# LTC3115_-_przetwornica_ogniwo.net
KiCad netlist of a schematic drawn in EAGLE
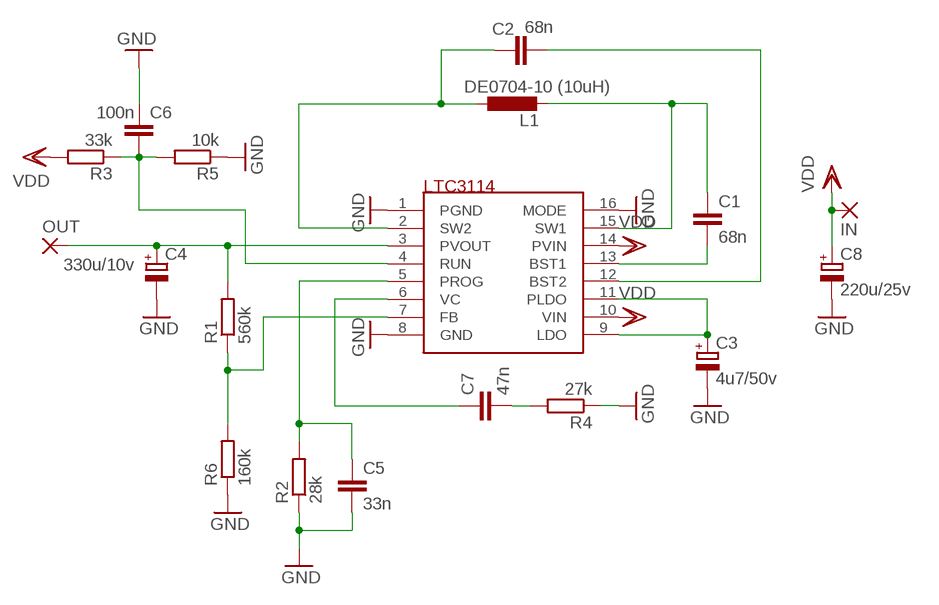
[diagram p0: schematic, sheet 1]

(export (version "E")
  (design (tool "Eeschema 10.0.6"))
  (components
    (comp (ref "C1")
      (value "68n")
      (footprint "eagle-import:C0805")
      (libsource (lib "eagle-import") (part "resistor_C-EUC0805"))
    )
    (comp (ref "C2")
      (value "68n")
      (footprint "eagle-import:C0805")
      (libsource (lib "eagle-import") (part "resistor_C-EUC0805"))
    )
    (comp (ref "C3")
      (value "4u7/50v")
      (footprint "eagle-import:E2,5-6E")
      (libsource (lib "eagle-import") (part "CPOL-EUE2,5-6E"))
    )
    (comp (ref "C4")
      (value "330u/10v")
      (footprint "eagle-import:E2,5-6E")
      (libsource (lib "eagle-import") (part "CPOL-EUE2,5-6E"))
    )
    (comp (ref "C5")
      (value "33n")
      (footprint "eagle-import:C0805")
      (libsource (lib "eagle-import") (part "C-EUC0805"))
    )
    (comp (ref "C6")
      (value "100n")
      (footprint "eagle-import:C0805")
      (libsource (lib "eagle-import") (part "C-EUC0805"))
    )
    (comp (ref "C7")
      (value "47n")
      (footprint "eagle-import:C0805")
      (libsource (lib "eagle-import") (part "C-EUC0805"))
    )
    (comp (ref "C8")
      (value "220u/25v")
      (footprint "eagle-import:E2,5-6E")
      (libsource (lib "eagle-import") (part "CPOL-EUE2,5-6E"))
    )
    (comp (ref "IN")
      (value "1,6/0,8")
      (footprint "eagle-import:1,6_0,8")
      (libsource (lib "eagle-import") (part "1,6/0,8"))
    )
    (comp (ref "L1")
      (value "DE0704-10 (10uH)")
      (footprint "eagle-import:L3225M")
      (libsource (lib "eagle-import") (part "L-EUL3225M"))
    )
    (comp (ref "OUT")
      (value "1,6/0,8")
      (footprint "eagle-import:1,6_0,8")
      (libsource (lib "eagle-import") (part "1,6/0,8"))
    )
    (comp (ref "R1")
      (value "560k")
      (footprint "eagle-import:M0805")
      (libsource (lib "eagle-import") (part "R-EU_M0805"))
    )
    (comp (ref "R2")
      (value "28k")
      (footprint "eagle-import:M0805")
      (libsource (lib "eagle-import") (part "R-EU_M0805"))
    )
    (comp (ref "R3")
      (value "33k")
      (footprint "eagle-import:M0805")
      (libsource (lib "eagle-import") (part "R-EU_M0805"))
    )
    (comp (ref "R4")
      (value "27k")
      (footprint "eagle-import:M0805")
      (libsource (lib "eagle-import") (part "R-EU_M0805"))
    )
    (comp (ref "R5")
      (value "10k")
      (footprint "eagle-import:M0805")
      (libsource (lib "eagle-import") (part "R-EU_M0805"))
    )
    (comp (ref "R6")
      (value "160k")
      (footprint "eagle-import:M0805")
      (libsource (lib "eagle-import") (part "R-EU_M0805"))
    )
    (comp (ref "U$1")
      (value "LTC3114")
      (footprint "eagle-import:TSSOP16")
      (libsource (lib "eagle-import") (part "LTC3114"))
    )
  )
  (nets
    (net (code "1") (name "GND") (class "Default")
      (node (ref "C3") (pin "-") (pinfunction "-_-") (pintype "passive"))
      (node (ref "C4") (pin "-") (pinfunction "-_-") (pintype "passive"))
      (node (ref "C5") (pin "2") (pinfunction "2_2") (pintype "passive"))
      (node (ref "C6") (pin "1") (pinfunction "1_1") (pintype "passive"))
      (node (ref "C8") (pin "-") (pinfunction "-_-") (pintype "passive"))
      (node (ref "R2") (pin "1") (pinfunction "1_1") (pintype "passive"))
      (node (ref "R4") (pin "1") (pinfunction "1_1") (pintype "passive"))
      (node (ref "R5") (pin "1") (pinfunction "1_1") (pintype "passive"))
      (node (ref "R6") (pin "1") (pinfunction "1_1") (pintype "passive"))
      (node (ref "U$1") (pin "1") (pinfunction "PGND_1") (pintype "bidirectional"))
      (node (ref "U$1") (pin "16") (pinfunction "MODE_16") (pintype "bidirectional"))
      (node (ref "U$1") (pin "8") (pinfunction "GND_8") (pintype "bidirectional"))
    )
    (net (code "2") (name "Net-(C7-Pad2)") (class "Default")
      (node (ref "C7") (pin "2") (pinfunction "2_2") (pintype "passive"))
      (node (ref "R4") (pin "2") (pinfunction "2_2") (pintype "passive"))
    )
    (net (code "3") (name "Net-(OUT-P)") (class "Default")
      (node (ref "C4") (pin "+") (pinfunction "+_+") (pintype "passive"))
      (node (ref "OUT") (pin "1") (pinfunction "P_1") (pintype "passive"))
      (node (ref "R1") (pin "2") (pinfunction "2_2") (pintype "passive"))
      (node (ref "U$1") (pin "3") (pinfunction "PVOUT_3") (pintype "bidirectional"))
    )
    (net (code "4") (name "Net-(U$1-BST1)") (class "Default")
      (node (ref "C1") (pin "2") (pinfunction "2_2") (pintype "passive"))
      (node (ref "U$1") (pin "13") (pinfunction "BST1_13") (pintype "bidirectional"))
    )
    (net (code "5") (name "Net-(U$1-BST2)") (class "Default")
      (node (ref "C2") (pin "1") (pinfunction "1_1") (pintype "passive"))
      (node (ref "U$1") (pin "12") (pinfunction "BST2_12") (pintype "bidirectional"))
    )
    (net (code "6") (name "Net-(U$1-FB)") (class "Default")
      (node (ref "R1") (pin "1") (pinfunction "1_1") (pintype "passive"))
      (node (ref "R6") (pin "2") (pinfunction "2_2") (pintype "passive"))
      (node (ref "U$1") (pin "7") (pinfunction "FB_7") (pintype "bidirectional"))
    )
    (net (code "7") (name "Net-(U$1-LDO)") (class "Default")
      (node (ref "C3") (pin "+") (pinfunction "+_+") (pintype "passive"))
      (node (ref "U$1") (pin "11") (pinfunction "PLDO_11") (pintype "bidirectional"))
      (node (ref "U$1") (pin "9") (pinfunction "LDO_9") (pintype "bidirectional"))
    )
    (net (code "8") (name "Net-(U$1-PROG)") (class "Default")
      (node (ref "C5") (pin "1") (pinfunction "1_1") (pintype "passive"))
      (node (ref "R2") (pin "2") (pinfunction "2_2") (pintype "passive"))
      (node (ref "U$1") (pin "5") (pinfunction "PROG_5") (pintype "bidirectional"))
    )
    (net (code "9") (name "Net-(U$1-RUN)") (class "Default")
      (node (ref "C6") (pin "2") (pinfunction "2_2") (pintype "passive"))
      (node (ref "R3") (pin "1") (pinfunction "1_1") (pintype "passive"))
      (node (ref "R5") (pin "2") (pinfunction "2_2") (pintype "passive"))
      (node (ref "U$1") (pin "4") (pinfunction "RUN_4") (pintype "bidirectional"))
    )
    (net (code "10") (name "Net-(U$1-SW1)") (class "Default")
      (node (ref "C1") (pin "1") (pinfunction "1_1") (pintype "passive"))
      (node (ref "L1") (pin "2") (pinfunction "2_2") (pintype "passive"))
      (node (ref "U$1") (pin "15") (pinfunction "SW1_15") (pintype "bidirectional"))
    )
    (net (code "11") (name "Net-(U$1-SW2)") (class "Default")
      (node (ref "C2") (pin "2") (pinfunction "2_2") (pintype "passive"))
      (node (ref "L1") (pin "1") (pinfunction "1_1") (pintype "passive"))
      (node (ref "U$1") (pin "2") (pinfunction "SW2_2") (pintype "bidirectional"))
    )
    (net (code "12") (name "Net-(U$1-VC)") (class "Default")
      (node (ref "C7") (pin "1") (pinfunction "1_1") (pintype "passive"))
      (node (ref "U$1") (pin "6") (pinfunction "VC_6") (pintype "bidirectional"))
    )
    (net (code "13") (name "VDD") (class "Default")
      (node (ref "C8") (pin "+") (pinfunction "+_+") (pintype "passive"))
      (node (ref "IN") (pin "1") (pinfunction "P_1") (pintype "passive"))
      (node (ref "R3") (pin "2") (pinfunction "2_2") (pintype "passive"))
      (node (ref "U$1") (pin "10") (pinfunction "VIN_10") (pintype "bidirectional"))
      (node (ref "U$1") (pin "14") (pinfunction "PVIN_14") (pintype "bidirectional"))
    )
  )
)
